# v4_1.net
KiCad netlist of a schematic drawn in EAGLE
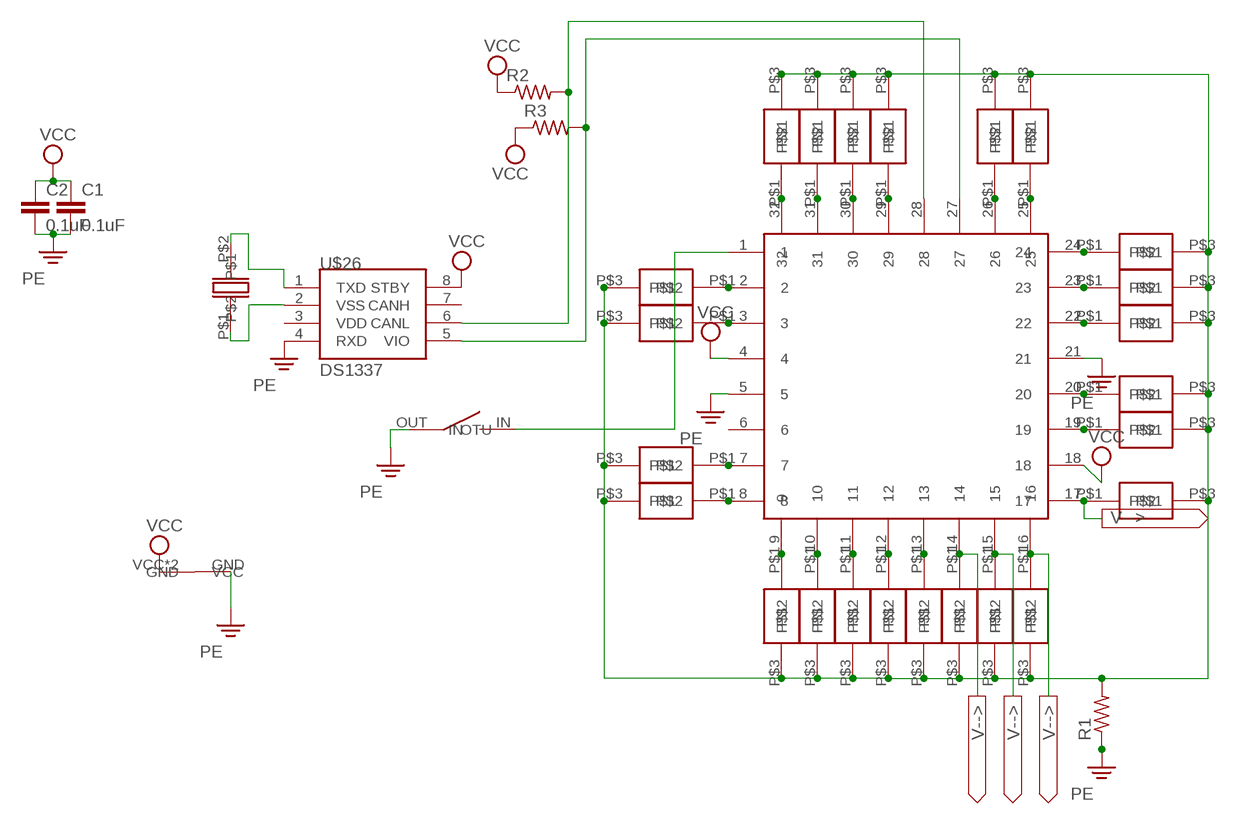
[diagram p0: schematic, sheet 1]

(export (version "E")
  (design (tool "Eeschema 10.0.6"))
  (components
    (comp (ref "C1")
      (value "0.1uF")
      (footprint "eagle-import:C0805K")
      (libsource (lib "eagle-import") (part "C-EUC0805K"))
    )
    (comp (ref "C2")
      (value "0.1uF")
      (footprint "eagle-import:C0805K")
      (libsource (lib "eagle-import") (part "C-EUC0805K"))
    )
    (comp (ref "R1")
      (value "R-US_R0805")
      (footprint "eagle-import:R0805")
      (libsource (lib "eagle-import") (part "R-US_R0805"))
    )
    (comp (ref "R2")
      (value "R-US_R0805")
      (footprint "eagle-import:R0805")
      (libsource (lib "eagle-import") (part "R-US_R0805"))
    )
    (comp (ref "R3")
      (value "R-US_R0805")
      (footprint "eagle-import:R0805")
      (libsource (lib "eagle-import") (part "R-US_R0805"))
    )
    (comp (ref "U$1")
      (value "SMDLED")
      (footprint "eagle-import:SMDLED")
      (libsource (lib "eagle-import") (part "SMDLED"))
    )
    (comp (ref "U$2")
      (value "SMDLED")
      (footprint "eagle-import:SMDLED")
      (libsource (lib "eagle-import") (part "SMDLED"))
    )
    (comp (ref "U$3")
      (value "SMDLED")
      (footprint "eagle-import:SMDLED")
      (libsource (lib "eagle-import") (part "SMDLED"))
    )
    (comp (ref "U$4")
      (value "SMDLED")
      (footprint "eagle-import:SMDLED")
      (libsource (lib "eagle-import") (part "SMDLED"))
    )
    (comp (ref "U$5")
      (value "SMDLED")
      (footprint "eagle-import:SMDLED")
      (libsource (lib "eagle-import") (part "SMDLED"))
    )
    (comp (ref "U$6")
      (value "SMDLED")
      (footprint "eagle-import:SMDLED")
      (libsource (lib "eagle-import") (part "SMDLED"))
    )
    (comp (ref "U$7")
      (value "SMDLED")
      (footprint "eagle-import:SMDLED")
      (libsource (lib "eagle-import") (part "SMDLED"))
    )
    (comp (ref "U$8")
      (value "SMDLED")
      (footprint "eagle-import:SMDLED")
      (libsource (lib "eagle-import") (part "SMDLED"))
    )
    (comp (ref "U$9")
      (value "SMDLED")
      (footprint "eagle-import:SMDLED")
      (libsource (lib "eagle-import") (part "SMDLED"))
    )
    (comp (ref "U$10")
      (value "SMDLED")
      (footprint "eagle-import:SMDLED")
      (libsource (lib "eagle-import") (part "SMDLED"))
    )
    (comp (ref "U$11")
      (value "SMDLED")
      (footprint "eagle-import:SMDLED")
      (libsource (lib "eagle-import") (part "SMDLED"))
    )
    (comp (ref "U$12")
      (value "SMDLED")
      (footprint "eagle-import:SMDLED")
      (libsource (lib "eagle-import") (part "SMDLED"))
    )
    (comp (ref "U$13")
      (value "SMDLED")
      (footprint "eagle-import:SMDLED")
      (libsource (lib "eagle-import") (part "SMDLED"))
    )
    (comp (ref "U$14")
      (value "SMDLED")
      (footprint "eagle-import:SMDLED")
      (libsource (lib "eagle-import") (part "SMDLED"))
    )
    (comp (ref "U$15")
      (value "SMDLED")
      (footprint "eagle-import:SMDLED")
      (libsource (lib "eagle-import") (part "SMDLED"))
    )
    (comp (ref "U$16")
      (value "SMDLED")
      (footprint "eagle-import:SMDLED")
      (libsource (lib "eagle-import") (part "SMDLED"))
    )
    (comp (ref "U$17")
      (value "SMDLED")
      (footprint "eagle-import:SMDLED")
      (libsource (lib "eagle-import") (part "SMDLED"))
    )
    (comp (ref "U$18")
      (value "SMDLED")
      (footprint "eagle-import:SMDLED")
      (libsource (lib "eagle-import") (part "SMDLED"))
    )
    (comp (ref "U$19")
      (value "SMDLED")
      (footprint "eagle-import:SMDLED")
      (libsource (lib "eagle-import") (part "SMDLED"))
    )
    (comp (ref "U$20")
      (value "SMDLED")
      (footprint "eagle-import:SMDLED")
      (libsource (lib "eagle-import") (part "SMDLED"))
    )
    (comp (ref "U$21")
      (value "SMDLED")
      (footprint "eagle-import:SMDLED")
      (libsource (lib "eagle-import") (part "SMDLED"))
    )
    (comp (ref "U$22")
      (value "SMDLED")
      (footprint "eagle-import:SMDLED")
      (libsource (lib "eagle-import") (part "SMDLED"))
    )
    (comp (ref "U$23")
      (value "SMDLED")
      (footprint "eagle-import:SMDLED")
      (libsource (lib "eagle-import") (part "SMDLED"))
    )
    (comp (ref "U$24")
      (value "SMDLED")
      (footprint "eagle-import:SMDLED")
      (libsource (lib "eagle-import") (part "SMDLED"))
    )
    (comp (ref "U$25")
      (value "ATTINY88")
      (footprint "eagle-import:32-TQFT")
      (libsource (lib "eagle-import") (part "ATTINY88"))
    )
    (comp (ref "U$26")
      (value "DS1337")
      (footprint "eagle-import:8-SOIC")
      (libsource (lib "eagle-import") (part "DS1337"))
    )
    (comp (ref "U$27")
      (value "BAT2009")
      (footprint "eagle-import:BAT2009")
      (libsource (lib "eagle-import") (part "BAT2009"))
    )
    (comp (ref "U$28")
      (value "INT2")
      (footprint "eagle-import:INT2")
      (libsource (lib "eagle-import") (part "INT2"))
    )
    (comp (ref "U$29")
      (value "SMDCRYSTAL")
      (footprint "eagle-import:SMDCRYSTAL")
      (libsource (lib "eagle-import") (part "SMDCRYSTAL"))
    )
  )
  (nets
    (net (code "1") (name "Net-(U$1-P$2)") (class "Default")
      (node (ref "R1") (pin "2") (pinfunction "2_2") (pintype "passive"))
      (node (ref "U$1") (pin "P$3") (pinfunction "P$2_P$3") (pintype "bidirectional"))
      (node (ref "U$10") (pin "P$3") (pinfunction "P$2_P$3") (pintype "bidirectional"))
      (node (ref "U$11") (pin "P$3") (pinfunction "P$2_P$3") (pintype "bidirectional"))
      (node (ref "U$12") (pin "P$3") (pinfunction "P$2_P$3") (pintype "bidirectional"))
      (node (ref "U$13") (pin "P$3") (pinfunction "P$2_P$3") (pintype "bidirectional"))
      (node (ref "U$14") (pin "P$3") (pinfunction "P$2_P$3") (pintype "bidirectional"))
      (node (ref "U$15") (pin "P$3") (pinfunction "P$2_P$3") (pintype "bidirectional"))
      (node (ref "U$16") (pin "P$3") (pinfunction "P$2_P$3") (pintype "bidirectional"))
      (node (ref "U$17") (pin "P$3") (pinfunction "P$2_P$3") (pintype "bidirectional"))
      (node (ref "U$18") (pin "P$3") (pinfunction "P$2_P$3") (pintype "bidirectional"))
      (node (ref "U$19") (pin "P$3") (pinfunction "P$2_P$3") (pintype "bidirectional"))
      (node (ref "U$2") (pin "P$3") (pinfunction "P$2_P$3") (pintype "bidirectional"))
      (node (ref "U$20") (pin "P$3") (pinfunction "P$2_P$3") (pintype "bidirectional"))
      (node (ref "U$21") (pin "P$3") (pinfunction "P$2_P$3") (pintype "bidirectional"))
      (node (ref "U$22") (pin "P$3") (pinfunction "P$2_P$3") (pintype "bidirectional"))
      (node (ref "U$23") (pin "P$3") (pinfunction "P$2_P$3") (pintype "bidirectional"))
      (node (ref "U$24") (pin "P$3") (pinfunction "P$2_P$3") (pintype "bidirectional"))
      (node (ref "U$3") (pin "P$3") (pinfunction "P$2_P$3") (pintype "bidirectional"))
      (node (ref "U$4") (pin "P$3") (pinfunction "P$2_P$3") (pintype "bidirectional"))
      (node (ref "U$5") (pin "P$3") (pinfunction "P$2_P$3") (pintype "bidirectional"))
      (node (ref "U$6") (pin "P$3") (pinfunction "P$2_P$3") (pintype "bidirectional"))
      (node (ref "U$7") (pin "P$3") (pinfunction "P$2_P$3") (pintype "bidirectional"))
      (node (ref "U$8") (pin "P$3") (pinfunction "P$2_P$3") (pintype "bidirectional"))
      (node (ref "U$9") (pin "P$3") (pinfunction "P$2_P$3") (pintype "bidirectional"))
    )
    (net (code "2") (name "Net-(U$1-PadP$1)") (class "Default")
      (node (ref "U$1") (pin "P$1") (pinfunction "P$1_P$1") (pintype "bidirectional"))
      (node (ref "U$25") (pin "12") (pinfunction "12_12") (pintype "bidirectional"))
    )
    (net (code "3") (name "Net-(U$2-PadP$1)") (class "Default")
      (node (ref "U$2") (pin "P$1") (pinfunction "P$1_P$1") (pintype "bidirectional"))
      (node (ref "U$25") (pin "13") (pinfunction "13_13") (pintype "bidirectional"))
    )
    (net (code "4") (name "Net-(U$10-PadP$1)") (class "Default")
      (node (ref "U$10") (pin "P$1") (pinfunction "P$1_P$1") (pintype "bidirectional"))
      (node (ref "U$25") (pin "20") (pinfunction "20_20") (pintype "bidirectional"))
    )
    (net (code "5") (name "Net-(U$11-PadP$1)") (class "Default")
      (node (ref "U$11") (pin "P$1") (pinfunction "P$1_P$1") (pintype "bidirectional"))
      (node (ref "U$25") (pin "17") (pinfunction "17_17") (pintype "bidirectional"))
    )
    (net (code "6") (name "Net-(U$12-PadP$1)") (class "Default")
      (node (ref "U$12") (pin "P$1") (pinfunction "P$1_P$1") (pintype "bidirectional"))
      (node (ref "U$25") (pin "19") (pinfunction "19_19") (pintype "bidirectional"))
    )
    (net (code "7") (name "Net-(U$13-PadP$1)") (class "Default")
      (node (ref "U$13") (pin "P$1") (pinfunction "P$1_P$1") (pintype "bidirectional"))
      (node (ref "U$25") (pin "30") (pinfunction "30_30") (pintype "bidirectional"))
    )
    (net (code "8") (name "Net-(U$14-PadP$1)") (class "Default")
      (node (ref "U$14") (pin "P$1") (pinfunction "P$1_P$1") (pintype "bidirectional"))
      (node (ref "U$25") (pin "31") (pinfunction "31_31") (pintype "bidirectional"))
    )
    (net (code "9") (name "Net-(U$15-PadP$1)") (class "Default")
      (node (ref "U$15") (pin "P$1") (pinfunction "P$1_P$1") (pintype "bidirectional"))
      (node (ref "U$25") (pin "32") (pinfunction "32_32") (pintype "bidirectional"))
    )
    (net (code "10") (name "Net-(U$16-PadP$1)") (class "Default")
      (node (ref "U$16") (pin "P$1") (pinfunction "P$1_P$1") (pintype "bidirectional"))
      (node (ref "U$25") (pin "2") (pinfunction "2_2") (pintype "bidirectional"))
    )
    (net (code "11") (name "Net-(U$17-PadP$1)") (class "Default")
      (node (ref "U$17") (pin "P$1") (pinfunction "P$1_P$1") (pintype "bidirectional"))
      (node (ref "U$25") (pin "3") (pinfunction "3_3") (pintype "bidirectional"))
    )
    (net (code "12") (name "Net-(U$18-PadP$1)") (class "Default")
      (node (ref "U$18") (pin "P$1") (pinfunction "P$1_P$1") (pintype "bidirectional"))
      (node (ref "U$25") (pin "9") (pinfunction "9_9") (pintype "bidirectional"))
    )
    (net (code "13") (name "Net-(U$19-PadP$1)") (class "Default")
      (node (ref "U$19") (pin "P$1") (pinfunction "P$1_P$1") (pintype "bidirectional"))
      (node (ref "U$25") (pin "10") (pinfunction "10_10") (pintype "bidirectional"))
    )
    (net (code "14") (name "Net-(U$20-PadP$1)") (class "Default")
      (node (ref "U$20") (pin "P$1") (pinfunction "P$1_P$1") (pintype "bidirectional"))
      (node (ref "U$25") (pin "11") (pinfunction "11_11") (pintype "bidirectional"))
    )
    (net (code "15") (name "Net-(U$21-PadP$1)") (class "Default")
      (node (ref "U$21") (pin "P$1") (pinfunction "P$1_P$1") (pintype "bidirectional"))
      (node (ref "U$25") (pin "22") (pinfunction "22_22") (pintype "bidirectional"))
    )
    (net (code "16") (name "Net-(U$22-PadP$1)") (class "Default")
      (node (ref "U$22") (pin "P$1") (pinfunction "P$1_P$1") (pintype "bidirectional"))
      (node (ref "U$25") (pin "23") (pinfunction "23_23") (pintype "bidirectional"))
    )
    (net (code "17") (name "Net-(U$23-PadP$1)") (class "Default")
      (node (ref "U$23") (pin "P$1") (pinfunction "P$1_P$1") (pintype "bidirectional"))
      (node (ref "U$25") (pin "29") (pinfunction "29_29") (pintype "bidirectional"))
    )
    (net (code "18") (name "Net-(U$24-PadP$1)") (class "Default")
      (node (ref "U$24") (pin "P$1") (pinfunction "P$1_P$1") (pintype "bidirectional"))
      (node (ref "U$25") (pin "26") (pinfunction "26_26") (pintype "bidirectional"))
    )
    (net (code "19") (name "Net-(U$25-Pad1)") (class "Default")
      (node (ref "U$25") (pin "1") (pinfunction "1_1") (pintype "bidirectional"))
      (node (ref "U$28") (pin "IN") (pinfunction "IN_IN") (pintype "bidirectional"))
    )
    (net (code "20") (name "Net-(U$25-Pad7)") (class "Default")
      (node (ref "U$25") (pin "7") (pinfunction "7_7") (pintype "bidirectional"))
      (node (ref "U$7") (pin "P$1") (pinfunction "P$1_P$1") (pintype "bidirectional"))
    )
    (net (code "21") (name "Net-(U$25-Pad8)") (class "Default")
      (node (ref "U$25") (pin "8") (pinfunction "8_8") (pintype "bidirectional"))
      (node (ref "U$8") (pin "P$1") (pinfunction "P$1_P$1") (pintype "bidirectional"))
    )
    (net (code "22") (name "Net-(U$25-Pad14)") (class "Default")
      (node (ref "U$25") (pin "14") (pinfunction "14_14") (pintype "bidirectional"))
      (node (ref "U$3") (pin "P$1") (pinfunction "P$1_P$1") (pintype "bidirectional"))
    )
    (net (code "23") (name "Net-(U$25-Pad15)") (class "Default")
      (node (ref "U$25") (pin "15") (pinfunction "15_15") (pintype "bidirectional"))
      (node (ref "U$4") (pin "P$1") (pinfunction "P$1_P$1") (pintype "bidirectional"))
    )
    (net (code "24") (name "Net-(U$25-Pad16)") (class "Default")
      (node (ref "U$25") (pin "16") (pinfunction "16_16") (pintype "bidirectional"))
      (node (ref "U$5") (pin "P$1") (pinfunction "P$1_P$1") (pintype "bidirectional"))
    )
    (net (code "25") (name "Net-(U$25-Pad24)") (class "Default")
      (node (ref "U$25") (pin "24") (pinfunction "24_24") (pintype "bidirectional"))
      (node (ref "U$6") (pin "P$1") (pinfunction "P$1_P$1") (pintype "bidirectional"))
    )
    (net (code "26") (name "Net-(U$25-Pad25)") (class "Default")
      (node (ref "U$25") (pin "25") (pinfunction "25_25") (pintype "bidirectional"))
      (node (ref "U$9") (pin "P$1") (pinfunction "P$1_P$1") (pintype "bidirectional"))
    )
    (net (code "27") (name "Net-(U$26-CANL)") (class "Default")
      (node (ref "R2") (pin "2") (pinfunction "2_2") (pintype "passive"))
      (node (ref "U$25") (pin "28") (pinfunction "28_28") (pintype "bidirectional"))
      (node (ref "U$26") (pin "6") (pinfunction "CANL_6") (pintype "bidirectional"))
    )
    (net (code "28") (name "Net-(U$26-TXD)") (class "Default")
      (node (ref "U$26") (pin "1") (pinfunction "TXD_1") (pintype "bidirectional"))
      (node (ref "U$29") (pin "P$2") (pinfunction "P$2_P$2") (pintype "bidirectional"))
    )
    (net (code "29") (name "Net-(U$26-VIO)") (class "Default")
      (node (ref "R3") (pin "2") (pinfunction "2_2") (pintype "passive"))
      (node (ref "U$25") (pin "27") (pinfunction "27_27") (pintype "bidirectional"))
      (node (ref "U$26") (pin "5") (pinfunction "VIO_5") (pintype "bidirectional"))
    )
    (net (code "30") (name "Net-(U$26-VSS)") (class "Default")
      (node (ref "U$26") (pin "2") (pinfunction "VSS_2") (pintype "bidirectional"))
      (node (ref "U$29") (pin "P$1") (pinfunction "P$1_P$1") (pintype "bidirectional"))
    )
    (net (code "31") (name "PE") (class "Default")
      (node (ref "C1") (pin "2") (pinfunction "2_2") (pintype "passive"))
      (node (ref "C2") (pin "2") (pinfunction "2_2") (pintype "passive"))
      (node (ref "R1") (pin "1") (pinfunction "1_1") (pintype "passive"))
      (node (ref "U$25") (pin "21") (pinfunction "21_21") (pintype "bidirectional"))
      (node (ref "U$25") (pin "5") (pinfunction "5_5") (pintype "bidirectional"))
      (node (ref "U$26") (pin "4") (pinfunction "RXD_4") (pintype "bidirectional"))
      (node (ref "U$27") (pin "GND") (pinfunction "GND_GND") (pintype "bidirectional"))
      (node (ref "U$28") (pin "OUT") (pinfunction "OTU_OUT") (pintype "bidirectional"))
    )
    (net (code "32") (name "VCC") (class "Default")
      (node (ref "C1") (pin "1") (pinfunction "1_1") (pintype "passive"))
      (node (ref "C2") (pin "1") (pinfunction "1_1") (pintype "passive"))
      (node (ref "R2") (pin "1") (pinfunction "1_1") (pintype "passive"))
      (node (ref "R3") (pin "1") (pinfunction "1_1") (pintype "passive"))
      (node (ref "U$25") (pin "18") (pinfunction "18_18") (pintype "bidirectional"))
      (node (ref "U$25") (pin "4") (pinfunction "4_4") (pintype "bidirectional"))
      (node (ref "U$26") (pin "8") (pinfunction "STBY_8") (pintype "bidirectional"))
      (node (ref "U$27") (pin "VCC") (pinfunction "VCC_VCC") (pintype "bidirectional"))
      (node (ref "U$27") (pin "VCC2") (pinfunction "VCC_VCC2") (pintype "bidirectional"))
    )
    (net (code "33") (name "unconnected-(U$25-Pad6)") (class "Default")
      (node (ref "U$25") (pin "6") (pinfunction "6_6") (pintype "bidirectional"))
    )
    (net (code "34") (name "unconnected-(U$26-CANH-Pad7)") (class "Default")
      (node (ref "U$26") (pin "7") (pinfunction "CANH_7") (pintype "bidirectional"))
    )
    (net (code "35") (name "unconnected-(U$26-VDD-Pad3)") (class "Default")
      (node (ref "U$26") (pin "3") (pinfunction "VDD_3") (pintype "bidirectional"))
    )
  )
)
